# mfl_modul_u6052b.net
KiCad netlist of a schematic drawn in EAGLE
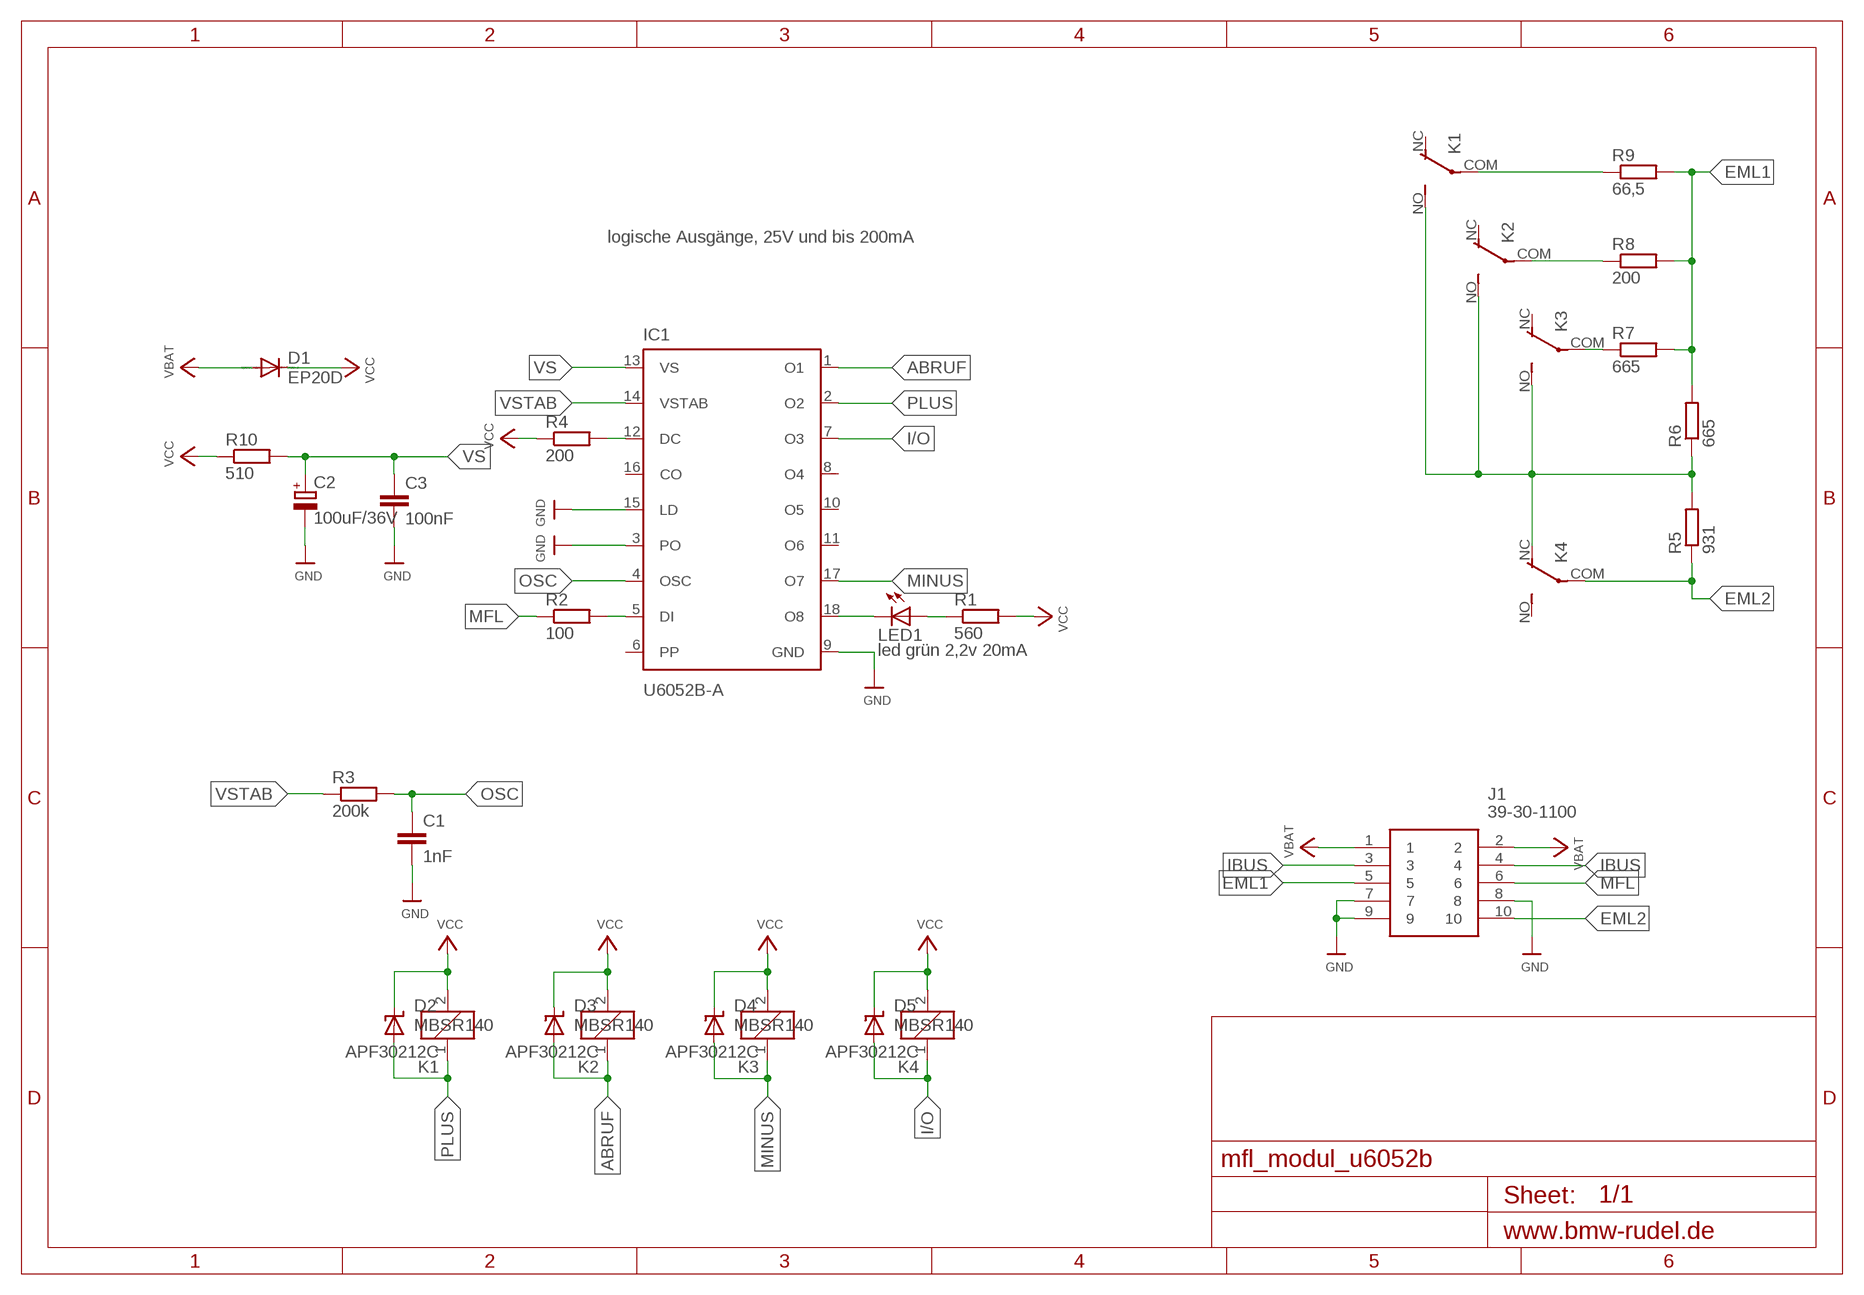
[diagram p0: schematic, sheet 1]

(export (version "E")
  (design (tool "Eeschema 10.0.6"))
  (components
    (comp (ref "C1")
      (value "1nF")
      (footprint "eagle-import:C025-025X050")
      (libsource (lib "eagle-import") (part "C-EU025-025X050"))
    )
    (comp (ref "C2")
      (value "100uF/36V")
      (footprint "eagle-import:E2,5-6")
      (libsource (lib "eagle-import") (part "CPOL-EUE2.5-6"))
    )
    (comp (ref "C3")
      (value "100nF")
      (footprint "eagle-import:C025-025X050")
      (libsource (lib "eagle-import") (part "C-EU025-025X050"))
    )
    (comp (ref "D1")
      (value "EP20D")
      (footprint "eagle-import:DO15-12")
      (libsource (lib "eagle-import") (part "DIODE-DO15-12"))
    )
    (comp (ref "D2")
      (value "MBSR140")
      (footprint "eagle-import:DO214AA")
      (libsource (lib "eagle-import") (part "SHOTKY-SMDSMB"))
    )
    (comp (ref "D3")
      (value "MBSR140")
      (footprint "eagle-import:DO214AA")
      (libsource (lib "eagle-import") (part "SHOTKY-SMDSMB"))
    )
    (comp (ref "D4")
      (value "MBSR140")
      (footprint "eagle-import:DO214AA")
      (libsource (lib "eagle-import") (part "SHOTKY-SMDSMB"))
    )
    (comp (ref "D5")
      (value "MBSR140")
      (footprint "eagle-import:DO214AA")
      (libsource (lib "eagle-import") (part "SHOTKY-SMDSMB"))
    )
    (comp (ref "IC1")
      (value "U6052B-A")
      (footprint "eagle-import:DIL18")
      (libsource (lib "eagle-import") (part "U6052B-A"))
    )
    (comp (ref "J1")
      (value "39-30-1100")
      (footprint "eagle-import:39-30-1100")
      (fields (field (name "MOUSER_PART_NUMBER") "538-39-30-1100") (field (name "RS_PART_NUMBER") "5109871P"))
      (libsource (lib "eagle-import") (part "39-30-1100"))
    )
    (comp (ref "K1")
      (value "APF30212C")
      (footprint "eagle-import:APF30212C")
      (libsource (lib "eagle-import") (part "APF30212C"))
    )
    (comp (ref "K2")
      (value "APF30212C")
      (footprint "eagle-import:APF30212C")
      (libsource (lib "eagle-import") (part "APF30212C"))
    )
    (comp (ref "K3")
      (value "APF30212C")
      (footprint "eagle-import:APF30212C")
      (libsource (lib "eagle-import") (part "APF30212C"))
    )
    (comp (ref "K4")
      (value "APF30212C")
      (footprint "eagle-import:APF30212C")
      (libsource (lib "eagle-import") (part "APF30212C"))
    )
    (comp (ref "LED1")
      (value "led grün 2,2v 20mA")
      (footprint "eagle-import:LED3MM")
      (libsource (lib "eagle-import") (part "LED3MM"))
    )
    (comp (ref "R1")
      (value "560")
      (footprint "eagle-import:0207_7")
      (libsource (lib "eagle-import") (part "R-EU_0207/7"))
    )
    (comp (ref "R2")
      (value "100")
      (footprint "eagle-import:0207_7")
      (libsource (lib "eagle-import") (part "R-EU_0207/7"))
    )
    (comp (ref "R3")
      (value "200k")
      (footprint "eagle-import:0207_7")
      (libsource (lib "eagle-import") (part "R-EU_0207/7"))
    )
    (comp (ref "R4")
      (value "200")
      (footprint "eagle-import:0207_7")
      (libsource (lib "eagle-import") (part "R-EU_0207/7"))
    )
    (comp (ref "R5")
      (value "931")
      (footprint "eagle-import:0207_7")
      (libsource (lib "eagle-import") (part "R-EU_0207/7"))
    )
    (comp (ref "R6")
      (value "665")
      (footprint "eagle-import:0207_7")
      (libsource (lib "eagle-import") (part "R-EU_0207/7"))
    )
    (comp (ref "R7")
      (value "665")
      (footprint "eagle-import:0207_7")
      (libsource (lib "eagle-import") (part "R-EU_0207/7"))
    )
    (comp (ref "R8")
      (value "200")
      (footprint "eagle-import:0207_7")
      (libsource (lib "eagle-import") (part "R-EU_0207/7"))
    )
    (comp (ref "R9")
      (value "66,5")
      (footprint "eagle-import:0207_7")
      (libsource (lib "eagle-import") (part "R-EU_0207/7"))
    )
    (comp (ref "R10")
      (value "510")
      (footprint "eagle-import:0207_7")
      (libsource (lib "eagle-import") (part "R-EU_0207/7"))
    )
  )
  (nets
    (net (code "1") (name "ABRUF") (class "Default")
      (node (ref "D3") (pin "A") (pinfunction "A_A") (pintype "passive"))
      (node (ref "IC1") (pin "1") (pinfunction "O1_1") (pintype "bidirectional"))
      (node (ref "K2") (pin "1") (pinfunction "1_1") (pintype "passive"))
    )
    (net (code "2") (name "EML1") (class "Default")
      (node (ref "J1") (pin "5") (pinfunction "5_5") (pintype "bidirectional"))
      (node (ref "R6") (pin "2") (pinfunction "2_2") (pintype "passive"))
      (node (ref "R7") (pin "2") (pinfunction "2_2") (pintype "passive"))
      (node (ref "R8") (pin "2") (pinfunction "2_2") (pintype "passive"))
      (node (ref "R9") (pin "2") (pinfunction "2_2") (pintype "passive"))
    )
    (net (code "3") (name "EML2") (class "Default")
      (node (ref "J1") (pin "10") (pinfunction "10_10") (pintype "bidirectional"))
      (node (ref "K4") (pin "COM") (pinfunction "P_COM") (pintype "passive"))
      (node (ref "R5") (pin "1") (pinfunction "1_1") (pintype "passive"))
    )
    (net (code "4") (name "GND") (class "Default")
      (node (ref "C1") (pin "2") (pinfunction "2_2") (pintype "passive"))
      (node (ref "C2") (pin "-") (pinfunction "-_-") (pintype "passive"))
      (node (ref "C3") (pin "2") (pinfunction "2_2") (pintype "passive"))
      (node (ref "IC1") (pin "15") (pinfunction "LD_15") (pintype "bidirectional"))
      (node (ref "IC1") (pin "3") (pinfunction "PO_3") (pintype "bidirectional"))
      (node (ref "IC1") (pin "9") (pinfunction "GND_9") (pintype "bidirectional"))
      (node (ref "J1") (pin "7") (pinfunction "7_7") (pintype "bidirectional"))
      (node (ref "J1") (pin "8") (pinfunction "8_8") (pintype "bidirectional"))
      (node (ref "J1") (pin "9") (pinfunction "9_9") (pintype "bidirectional"))
    )
    (net (code "5") (name "IBUS") (class "Default")
      (node (ref "J1") (pin "3") (pinfunction "3_3") (pintype "bidirectional"))
      (node (ref "J1") (pin "4") (pinfunction "4_4") (pintype "bidirectional"))
    )
    (net (code "6") (name "I{slash}O") (class "Default")
      (node (ref "D5") (pin "A") (pinfunction "A_A") (pintype "passive"))
      (node (ref "IC1") (pin "7") (pinfunction "O3_7") (pintype "bidirectional"))
      (node (ref "K4") (pin "1") (pinfunction "1_1") (pintype "passive"))
    )
    (net (code "7") (name "MFL") (class "Default")
      (node (ref "J1") (pin "6") (pinfunction "6_6") (pintype "bidirectional"))
      (node (ref "R2") (pin "1") (pinfunction "1_1") (pintype "passive"))
    )
    (net (code "8") (name "MINUS") (class "Default")
      (node (ref "D4") (pin "A") (pinfunction "A_A") (pintype "passive"))
      (node (ref "IC1") (pin "17") (pinfunction "O7_17") (pintype "bidirectional"))
      (node (ref "K3") (pin "1") (pinfunction "1_1") (pintype "passive"))
    )
    (net (code "9") (name "Net-(IC1-DC)") (class "Default")
      (node (ref "IC1") (pin "12") (pinfunction "DC_12") (pintype "bidirectional"))
      (node (ref "R4") (pin "2") (pinfunction "2_2") (pintype "passive"))
    )
    (net (code "10") (name "Net-(IC1-DI)") (class "Default")
      (node (ref "IC1") (pin "5") (pinfunction "DI_5") (pintype "bidirectional"))
      (node (ref "R2") (pin "2") (pinfunction "2_2") (pintype "passive"))
    )
    (net (code "11") (name "Net-(IC1-O8)") (class "Default")
      (node (ref "IC1") (pin "18") (pinfunction "O8_18") (pintype "bidirectional"))
      (node (ref "LED1") (pin "K") (pinfunction "C_K") (pintype "passive"))
    )
    (net (code "12") (name "Net-(K1B-P)") (class "Default")
      (node (ref "K1") (pin "COM") (pinfunction "P_COM") (pintype "passive"))
      (node (ref "R9") (pin "1") (pinfunction "1_1") (pintype "passive"))
    )
    (net (code "13") (name "Net-(K1B-S)") (class "Default")
      (node (ref "K1") (pin "NO") (pinfunction "S_NO") (pintype "passive"))
      (node (ref "K2") (pin "NO") (pinfunction "S_NO") (pintype "passive"))
      (node (ref "K3") (pin "NO") (pinfunction "S_NO") (pintype "passive"))
      (node (ref "K4") (pin "NC") (pinfunction "O_NC") (pintype "passive"))
      (node (ref "R5") (pin "2") (pinfunction "2_2") (pintype "passive"))
      (node (ref "R6") (pin "1") (pinfunction "1_1") (pintype "passive"))
    )
    (net (code "14") (name "Net-(K2B-P)") (class "Default")
      (node (ref "K2") (pin "COM") (pinfunction "P_COM") (pintype "passive"))
      (node (ref "R8") (pin "1") (pinfunction "1_1") (pintype "passive"))
    )
    (net (code "15") (name "Net-(K3B-P)") (class "Default")
      (node (ref "K3") (pin "COM") (pinfunction "P_COM") (pintype "passive"))
      (node (ref "R7") (pin "1") (pinfunction "1_1") (pintype "passive"))
    )
    (net (code "16") (name "Net-(LED1-PadA)") (class "Default")
      (node (ref "LED1") (pin "A") (pinfunction "A_A") (pintype "passive"))
      (node (ref "R1") (pin "1") (pinfunction "1_1") (pintype "passive"))
    )
    (net (code "17") (name "OSC") (class "Default")
      (node (ref "C1") (pin "1") (pinfunction "1_1") (pintype "passive"))
      (node (ref "IC1") (pin "4") (pinfunction "OSC_4") (pintype "bidirectional"))
      (node (ref "R3") (pin "2") (pinfunction "2_2") (pintype "passive"))
    )
    (net (code "18") (name "PLUS") (class "Default")
      (node (ref "D2") (pin "A") (pinfunction "A_A") (pintype "passive"))
      (node (ref "IC1") (pin "2") (pinfunction "O2_2") (pintype "bidirectional"))
      (node (ref "K1") (pin "1") (pinfunction "1_1") (pintype "passive"))
    )
    (net (code "19") (name "VBAT") (class "Default")
      (node (ref "D1") (pin "A") (pinfunction "A_A") (pintype "passive"))
      (node (ref "J1") (pin "1") (pinfunction "1_1") (pintype "bidirectional"))
      (node (ref "J1") (pin "2") (pinfunction "2_2") (pintype "bidirectional"))
    )
    (net (code "20") (name "VCC") (class "Default")
      (node (ref "D1") (pin "C") (pinfunction "C_C") (pintype "passive"))
      (node (ref "D2") (pin "C") (pinfunction "C_C") (pintype "passive"))
      (node (ref "D3") (pin "C") (pinfunction "C_C") (pintype "passive"))
      (node (ref "D4") (pin "C") (pinfunction "C_C") (pintype "passive"))
      (node (ref "D5") (pin "C") (pinfunction "C_C") (pintype "passive"))
      (node (ref "K1") (pin "2") (pinfunction "2_2") (pintype "passive"))
      (node (ref "K2") (pin "2") (pinfunction "2_2") (pintype "passive"))
      (node (ref "K3") (pin "2") (pinfunction "2_2") (pintype "passive"))
      (node (ref "K4") (pin "2") (pinfunction "2_2") (pintype "passive"))
      (node (ref "R1") (pin "2") (pinfunction "2_2") (pintype "passive"))
      (node (ref "R10") (pin "1") (pinfunction "1_1") (pintype "passive"))
      (node (ref "R4") (pin "1") (pinfunction "1_1") (pintype "passive"))
    )
    (net (code "21") (name "VS") (class "Default")
      (node (ref "C2") (pin "+") (pinfunction "+_+") (pintype "passive"))
      (node (ref "C3") (pin "1") (pinfunction "1_1") (pintype "passive"))
      (node (ref "IC1") (pin "13") (pinfunction "VS_13") (pintype "bidirectional"))
      (node (ref "R10") (pin "2") (pinfunction "2_2") (pintype "passive"))
    )
    (net (code "22") (name "VSTAB") (class "Default")
      (node (ref "IC1") (pin "14") (pinfunction "VSTAB_14") (pintype "bidirectional"))
      (node (ref "R3") (pin "1") (pinfunction "1_1") (pintype "passive"))
    )
    (net (code "23") (name "unconnected-(IC1-CO-Pad16)") (class "Default")
      (node (ref "IC1") (pin "16") (pinfunction "CO_16") (pintype "bidirectional"))
    )
    (net (code "24") (name "unconnected-(IC1-O4-Pad8)") (class "Default")
      (node (ref "IC1") (pin "8") (pinfunction "O4_8") (pintype "bidirectional"))
    )
    (net (code "25") (name "unconnected-(IC1-O5-Pad10)") (class "Default")
      (node (ref "IC1") (pin "10") (pinfunction "O5_10") (pintype "bidirectional"))
    )
    (net (code "26") (name "unconnected-(IC1-O6-Pad11)") (class "Default")
      (node (ref "IC1") (pin "11") (pinfunction "O6_11") (pintype "bidirectional"))
    )
    (net (code "27") (name "unconnected-(IC1-PP-Pad6)") (class "Default")
      (node (ref "IC1") (pin "6") (pinfunction "PP_6") (pintype "bidirectional"))
    )
    (net (code "28") (name "unconnected-(K1B-O-PadNC)") (class "Default")
      (node (ref "K1") (pin "NC") (pinfunction "O_NC") (pintype "passive"))
    )
    (net (code "29") (name "unconnected-(K2B-O-PadNC)") (class "Default")
      (node (ref "K2") (pin "NC") (pinfunction "O_NC") (pintype "passive"))
    )
    (net (code "30") (name "unconnected-(K3B-O-PadNC)") (class "Default")
      (node (ref "K3") (pin "NC") (pinfunction "O_NC") (pintype "passive"))
    )
    (net (code "31") (name "unconnected-(K4B-S-PadNO)") (class "Default")
      (node (ref "K4") (pin "NO") (pinfunction "S_NO") (pintype "passive"))
    )
  )
)
